# MCU.net
KiCad netlist of a schematic drawn in Altium Designer
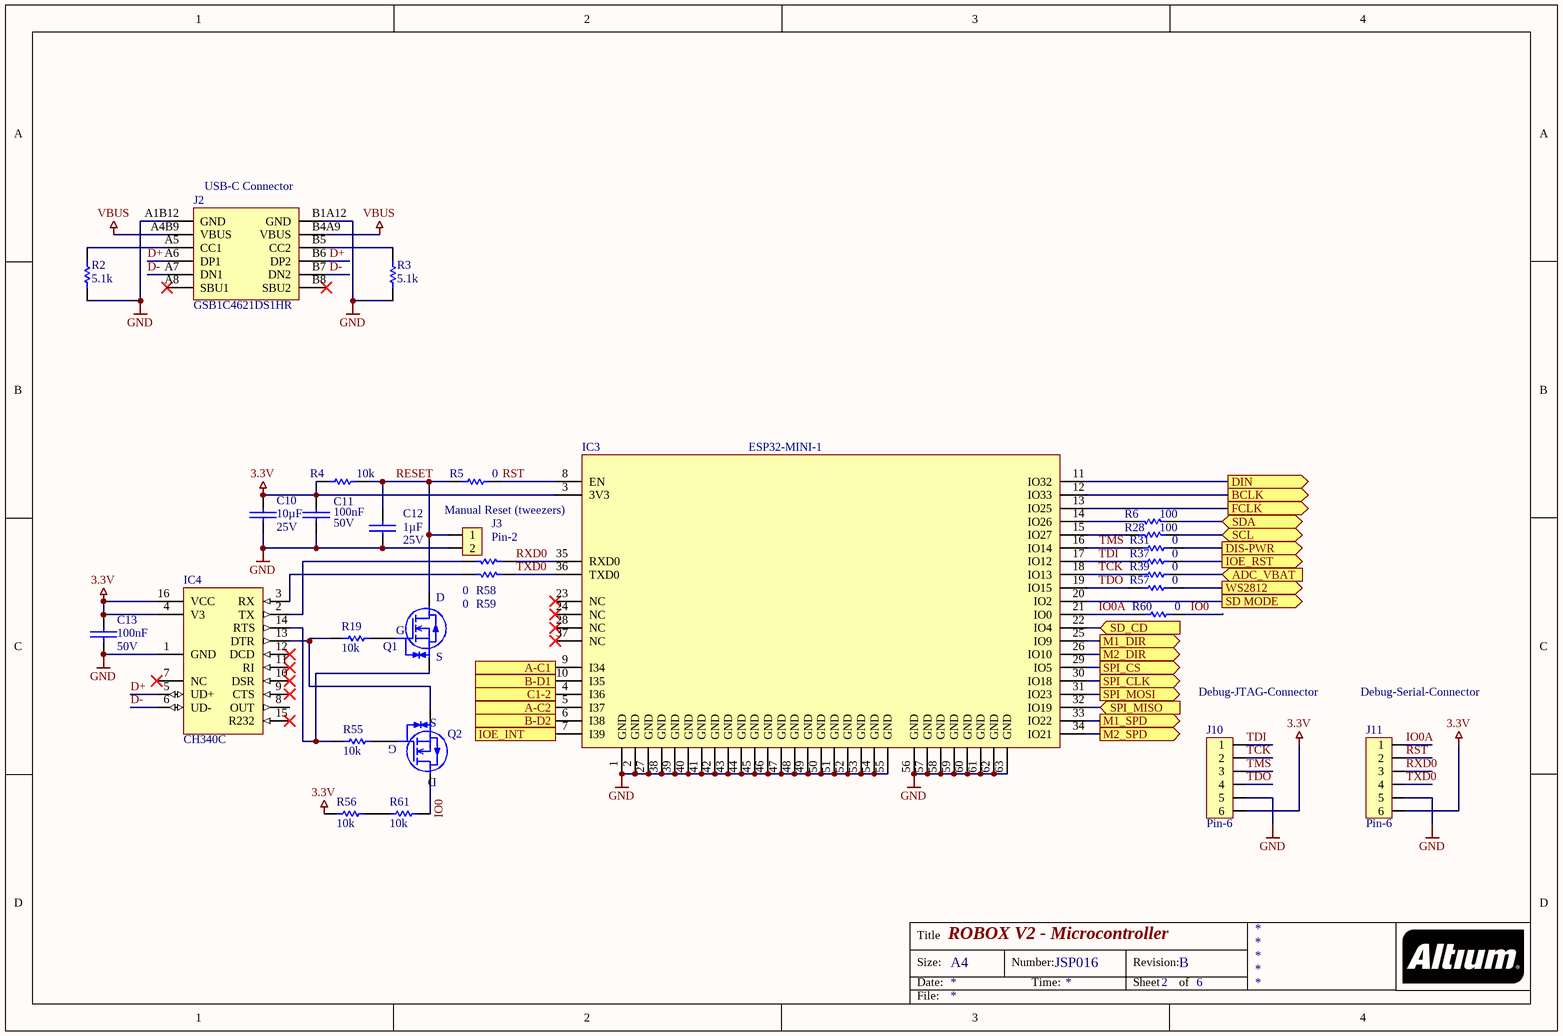
[diagram p0: MCU.SchDoc]

(export (version "E")
  (design (tool "Eeschema 10.0.6"))
  (components
    (comp (ref "C10")
      (value "10µF")
      (footprint "C0603")
      (description "CAP CER 10UF 25V X5R 10% SMD")
      (fields
        (field (name "MANUFACTURER") "Murata Electronics")
        (field (name "TOLERANCE") "10%")
        (field (name "VOLTAGE") "25V")
      )
      (libsource (lib "bond-altium-excell") (part "cap_non_pol"))
    )
    (comp (ref "C11")
      (value "100nF")
      (footprint "C0402")
      (description "CAP CER 0.1UF 50V X5R 0402")
      (fields
        (field (name "MANUFACTURER") "Murata Electronics")
        (field (name "TOLERANCE") "5%")
        (field (name "VOLTAGE") "50V")
      )
      (libsource (lib "bond-altium-excell") (part "cap_non_pol"))
    )
    (comp (ref "C12")
      (value "1µF")
      (footprint "C0603")
      (description "CAP CER 1UF 25V X5R 0603")
      (fields
        (field (name "MANUFACTURER") "YAGEO")
        (field (name "TOLERANCE") "10%")
        (field (name "VOLTAGE") "25V")
      )
      (libsource (lib "bond-altium-excell") (part "cap_non_pol"))
    )
    (comp (ref "C13")
      (value "100nF")
      (footprint "TH5.08")
      (description "CAP CER TH 100nF X7R 50V")
      (fields
        (field (name "MANUFACTURER") "FH")
        (field (name "TOLERANCE") "10%")
        (field (name "VOLTAGE") "50V")
      )
      (libsource (lib "bond-altium-excell") (part "cap_non_pol"))
    )
    (comp (ref "IC3")
      (value "ESP32-MINI-1")
      (footprint "ESP32-MINI-1")
      (description "RF TXRX MOD BT TRACE ANT CHAS MT")
      (fields (field (name "MANUFACTURER") "Espressif Systems"))
      (libsource (lib "bond-altium-excell") (part "ESP32-MINI-1"))
    )
    (comp (ref "IC4")
      (value "CH340C")
      (footprint "SOP-16")
      (description "2Mbps Transceiver USB 2.0 SOP-16 USB ICs ROHS")
      (fields (field (name "MANUFACTURER") "WCH(Jiangsu Qin Heng)"))
      (libsource (lib "bond-altium-excell") (part "CH340C"))
    )
    (comp (ref "J2")
      (value "GSB1C4621DS1HR")
      (footprint "GSB1C4621DS1HR")
      (description "USB2.0, TYPE C, MID MOUNT, CENTE")
      (fields (field (name "MANUFACTURER") "Amphenol ICC (Commercial Products)"))
      (libsource (lib "bond-altium-excell") (part "GSB1C4621DS1HR"))
    )
    (comp (ref "J3")
      (value "Pin-2")
      (footprint "2-PIN-EMPTY")
      (description "CONN TH solder pad")
      (libsource (lib "bond-altium-excell") (part "Pin-2"))
    )
    (comp (ref "J10")
      (value "Pin-6")
      (footprint "6-PIN-EMPTY")
      (description "CONN TH solder pad")
      (libsource (lib "bond-altium-excell") (part "Pin-6"))
    )
    (comp (ref "J11")
      (value "Pin-6")
      (footprint "6-PIN-EMPTY")
      (description "CONN TH solder pad")
      (libsource (lib "bond-altium-excell") (part "Pin-6"))
    )
    (comp (ref "Q1")
      (value "N_CH_MOSFET")
      (footprint "SOT-23(-3)")
      (description "MOSFET N-CH 100V 170MA SOT23-3")
      (fields (field (name "MANUFACTURER") "Diodes Incorporated"))
      (libsource (lib "bond-altium-excell") (part "N_CH_MOSFET"))
    )
    (comp (ref "Q2")
      (value "N_CH_MOSFET")
      (footprint "SOT-23(-3)")
      (description "MOSFET N-CH 100V 170MA SOT23-3")
      (fields (field (name "MANUFACTURER") "Diodes Incorporated"))
      (libsource (lib "bond-altium-excell") (part "N_CH_MOSFET"))
    )
    (comp (ref "R2")
      (value "5.1k")
      (footprint "R0402")
      (description "RES 5.1K OHM 1% 1/16W 0402")
      (fields (field (name "MANUFACTURER") "Stackpole Electronics Inc") (field (name "TOLERANCE") "1%"))
      (libsource (lib "bond-altium-excell") (part "resistor"))
    )
    (comp (ref "R3")
      (value "5.1k")
      (footprint "R0402")
      (description "RES 5.1K OHM 1% 1/16W 0402")
      (fields (field (name "MANUFACTURER") "Stackpole Electronics Inc") (field (name "TOLERANCE") "1%"))
      (libsource (lib "bond-altium-excell") (part "resistor"))
    )
    (comp (ref "R4")
      (value "10k")
      (footprint "R0402")
      (description "RES SMD 10K OHM 1% 1/10W 0402")
      (fields (field (name "MANUFACTURER") "Panasonic Electronic Components") (field (name "TOLERANCE") "1%"))
      (libsource (lib "bond-altium-excell") (part "resistor"))
    )
    (comp (ref "R5")
      (value "0")
      (footprint "R0402")
      (description "RES SMD 0 OHM JUMPER 1/10W 0402")
      (fields (field (name "MANUFACTURER") "Panasonic Electronic Components") (field (name "TOLERANCE") "1%"))
      (libsource (lib "bond-altium-excell") (part "resistor"))
    )
    (comp (ref "R6")
      (value "100")
      (footprint "R0402")
      (description "RES SMD 100 OHM 1% 1/5W 0402")
      (fields (field (name "MANUFACTURER") "Vishay Dale") (field (name "TOLERANCE") "1%"))
      (libsource (lib "bond-altium-excell") (part "resistor"))
    )
    (comp (ref "R19")
      (value "10k")
      (footprint "R0402")
      (description "RES SMD 10K OHM 1% 1/10W 0402")
      (fields (field (name "MANUFACTURER") "Panasonic Electronic Components") (field (name "TOLERANCE") "1%"))
      (libsource (lib "bond-altium-excell") (part "resistor"))
    )
    (comp (ref "R28")
      (value "100")
      (footprint "R0402")
      (description "RES SMD 100 OHM 1% 1/5W 0402")
      (fields (field (name "MANUFACTURER") "Vishay Dale") (field (name "TOLERANCE") "1%"))
      (libsource (lib "bond-altium-excell") (part "resistor"))
    )
    (comp (ref "R31")
      (value "0")
      (footprint "R0402")
      (description "RES SMD 0 OHM JUMPER 1/10W 0402")
      (fields (field (name "MANUFACTURER") "Panasonic Electronic Components") (field (name "TOLERANCE") "1%"))
      (libsource (lib "bond-altium-excell") (part "resistor"))
    )
    (comp (ref "R37")
      (value "0")
      (footprint "R0402")
      (description "RES SMD 0 OHM JUMPER 1/10W 0402")
      (fields (field (name "MANUFACTURER") "Panasonic Electronic Components") (field (name "TOLERANCE") "1%"))
      (libsource (lib "bond-altium-excell") (part "resistor"))
    )
    (comp (ref "R39")
      (value "0")
      (footprint "R0402")
      (description "RES SMD 0 OHM JUMPER 1/10W 0402")
      (fields (field (name "MANUFACTURER") "Panasonic Electronic Components") (field (name "TOLERANCE") "1%"))
      (libsource (lib "bond-altium-excell") (part "resistor"))
    )
    (comp (ref "R55")
      (value "10k")
      (footprint "R0402")
      (description "RES SMD 10K OHM 1% 1/10W 0402")
      (fields (field (name "MANUFACTURER") "Panasonic Electronic Components") (field (name "TOLERANCE") "1%"))
      (libsource (lib "bond-altium-excell") (part "resistor"))
    )
    (comp (ref "R56")
      (value "10k")
      (footprint "R0402")
      (description "RES SMD 10K OHM 1% 1/10W 0402")
      (fields (field (name "MANUFACTURER") "Panasonic Electronic Components") (field (name "TOLERANCE") "1%"))
      (libsource (lib "bond-altium-excell") (part "resistor"))
    )
    (comp (ref "R57")
      (value "0")
      (footprint "R0402")
      (description "RES SMD 0 OHM JUMPER 1/10W 0402")
      (fields (field (name "MANUFACTURER") "Panasonic Electronic Components") (field (name "TOLERANCE") "1%"))
      (libsource (lib "bond-altium-excell") (part "resistor"))
    )
    (comp (ref "R58")
      (value "0")
      (footprint "R0402")
      (description "RES SMD 0 OHM JUMPER 1/10W 0402")
      (fields (field (name "MANUFACTURER") "Panasonic Electronic Components") (field (name "TOLERANCE") "1%"))
      (libsource (lib "bond-altium-excell") (part "resistor"))
    )
    (comp (ref "R59")
      (value "0")
      (footprint "R0402")
      (description "RES SMD 0 OHM JUMPER 1/10W 0402")
      (fields (field (name "MANUFACTURER") "Panasonic Electronic Components") (field (name "TOLERANCE") "1%"))
      (libsource (lib "bond-altium-excell") (part "resistor"))
    )
    (comp (ref "R60")
      (value "0")
      (footprint "R0402")
      (description "RES SMD 0 OHM JUMPER 1/10W 0402")
      (fields (field (name "MANUFACTURER") "Panasonic Electronic Components") (field (name "TOLERANCE") "1%"))
      (libsource (lib "bond-altium-excell") (part "resistor"))
    )
    (comp (ref "R61")
      (value "10k")
      (footprint "R0402")
      (description "RES SMD 10K OHM 1% 1/10W 0402")
      (fields (field (name "MANUFACTURER") "Panasonic Electronic Components") (field (name "TOLERANCE") "1%"))
      (libsource (lib "bond-altium-excell") (part "resistor"))
    )
  )
  (nets
    (net (code "1") (name "/A-C1") (class "Default")
      (node (ref "IC3") (pin "9") (pinfunction "I34_9") (pintype "passive"))
    )
    (net (code "2") (name "/A-C2") (class "Default")
      (node (ref "IC3") (pin "5") (pinfunction "I37_5") (pintype "passive"))
    )
    (net (code "3") (name "/ADC_VBAT") (class "Default")
      (node (ref "R39") (pin "1") (pinfunction "1_1") (pintype "passive"))
    )
    (net (code "4") (name "/B-D1") (class "Default")
      (node (ref "IC3") (pin "10") (pinfunction "I35_10") (pintype "passive"))
    )
    (net (code "5") (name "/B-D2") (class "Default")
      (node (ref "IC3") (pin "6") (pinfunction "I38_6") (pintype "passive"))
    )
    (net (code "6") (name "/BCLK") (class "Default")
      (node (ref "IC3") (pin "12") (pinfunction "IO33_12") (pintype "passive"))
    )
    (net (code "7") (name "/C1-2") (class "Default")
      (node (ref "IC3") (pin "4") (pinfunction "I36_4") (pintype "passive"))
    )
    (net (code "8") (name "/D+") (class "Default")
      (node (ref "IC4") (pin "5") (pinfunction "UD+_5") (pintype "bidirectional"))
      (node (ref "J2") (pin "A6") (pinfunction "DP1_A6") (pintype "passive"))
      (node (ref "J2") (pin "B6") (pinfunction "DP2_B6") (pintype "passive"))
    )
    (net (code "9") (name "/D-") (class "Default")
      (node (ref "IC4") (pin "6") (pinfunction "UD-_6") (pintype "bidirectional"))
      (node (ref "J2") (pin "A7") (pinfunction "DN1_A7") (pintype "passive"))
      (node (ref "J2") (pin "B7") (pinfunction "DN2_B7") (pintype "passive"))
    )
    (net (code "10") (name "/DIN") (class "Default")
      (node (ref "IC3") (pin "11") (pinfunction "IO32_11") (pintype "passive"))
    )
    (net (code "11") (name "/DIS-PWR") (class "Default")
      (node (ref "R31") (pin "1") (pinfunction "1_1") (pintype "passive"))
    )
    (net (code "12") (name "/FCLK") (class "Default")
      (node (ref "IC3") (pin "13") (pinfunction "IO25_13") (pintype "passive"))
    )
    (net (code "13") (name "/IO0") (class "Default")
      (node (ref "Q2") (pin "3") (pinfunction "D_3") (pintype "passive"))
      (node (ref "R60") (pin "1") (pinfunction "1_1") (pintype "passive"))
      (node (ref "R61") (pin "2") (pinfunction "2_2") (pintype "passive"))
    )
    (net (code "14") (name "/IO0A") (class "Default")
      (node (ref "IC3") (pin "21") (pinfunction "IO0_21") (pintype "passive"))
      (node (ref "J11") (pin "1") (pinfunction "1_1") (pintype "passive"))
      (node (ref "R60") (pin "2") (pinfunction "2_2") (pintype "passive"))
    )
    (net (code "15") (name "/IOE_INT") (class "Default")
      (node (ref "IC3") (pin "7") (pinfunction "I39_7") (pintype "passive"))
    )
    (net (code "16") (name "/IOE_RST") (class "Default")
      (node (ref "R37") (pin "1") (pinfunction "1_1") (pintype "passive"))
    )
    (net (code "17") (name "/M1_DIR") (class "Default")
      (node (ref "IC3") (pin "25") (pinfunction "IO9_25") (pintype "passive"))
    )
    (net (code "18") (name "/M1_SPD") (class "Default")
      (node (ref "IC3") (pin "33") (pinfunction "IO22_33") (pintype "passive"))
    )
    (net (code "19") (name "/M2_DIR") (class "Default")
      (node (ref "IC3") (pin "26") (pinfunction "IO10_26") (pintype "passive"))
    )
    (net (code "20") (name "/M2_SPD") (class "Default")
      (node (ref "IC3") (pin "34") (pinfunction "IO21_34") (pintype "passive"))
    )
    (net (code "21") (name "/RESET") (class "Default")
      (node (ref "C12") (pin "1") (pinfunction "1_1") (pintype "passive"))
      (node (ref "J3") (pin "1") (pinfunction "1_1") (pintype "passive"))
      (node (ref "Q1") (pin "3") (pinfunction "D_3") (pintype "passive"))
      (node (ref "R4") (pin "1") (pinfunction "1_1") (pintype "passive"))
      (node (ref "R5") (pin "2") (pinfunction "2_2") (pintype "passive"))
    )
    (net (code "22") (name "/RST") (class "Default")
      (node (ref "IC3") (pin "8") (pinfunction "EN_8") (pintype "passive"))
      (node (ref "J11") (pin "2") (pinfunction "2_2") (pintype "passive"))
      (node (ref "R5") (pin "1") (pinfunction "1_1") (pintype "passive"))
    )
    (net (code "23") (name "/RXD0") (class "Default")
      (node (ref "IC3") (pin "35") (pinfunction "RXD0_35") (pintype "passive"))
      (node (ref "J11") (pin "3") (pinfunction "3_3") (pintype "passive"))
      (node (ref "R58") (pin "1") (pinfunction "1_1") (pintype "passive"))
    )
    (net (code "24") (name "/SCL") (class "Default")
      (node (ref "R28") (pin "2") (pinfunction "2_2") (pintype "passive"))
    )
    (net (code "25") (name "/SD MODE") (class "Default")
      (node (ref "IC3") (pin "20") (pinfunction "IO2_20") (pintype "passive"))
    )
    (net (code "26") (name "/SDA") (class "Default")
      (node (ref "R6") (pin "2") (pinfunction "2_2") (pintype "passive"))
    )
    (net (code "27") (name "/SD_CD") (class "Default")
      (node (ref "IC3") (pin "22") (pinfunction "IO4_22") (pintype "passive"))
    )
    (net (code "28") (name "/SPI_CLK") (class "Default")
      (node (ref "IC3") (pin "30") (pinfunction "IO18_30") (pintype "passive"))
    )
    (net (code "29") (name "/SPI_CS") (class "Default")
      (node (ref "IC3") (pin "29") (pinfunction "IO5_29") (pintype "passive"))
    )
    (net (code "30") (name "/SPI_MISO") (class "Default")
      (node (ref "IC3") (pin "32") (pinfunction "IO19_32") (pintype "passive"))
    )
    (net (code "31") (name "/SPI_MOSI") (class "Default")
      (node (ref "IC3") (pin "31") (pinfunction "IO23_31") (pintype "passive"))
    )
    (net (code "32") (name "/TCK") (class "Default")
      (node (ref "IC3") (pin "18") (pinfunction "IO13_18") (pintype "passive"))
      (node (ref "J10") (pin "2") (pinfunction "2_2") (pintype "passive"))
      (node (ref "R39") (pin "2") (pinfunction "2_2") (pintype "passive"))
    )
    (net (code "33") (name "/TDI") (class "Default")
      (node (ref "IC3") (pin "17") (pinfunction "IO12_17") (pintype "passive"))
      (node (ref "J10") (pin "1") (pinfunction "1_1") (pintype "passive"))
      (node (ref "R37") (pin "2") (pinfunction "2_2") (pintype "passive"))
    )
    (net (code "34") (name "/TDO") (class "Default")
      (node (ref "IC3") (pin "19") (pinfunction "IO15_19") (pintype "passive"))
      (node (ref "J10") (pin "4") (pinfunction "4_4") (pintype "passive"))
      (node (ref "R57") (pin "2") (pinfunction "2_2") (pintype "passive"))
    )
    (net (code "35") (name "/TMS") (class "Default")
      (node (ref "IC3") (pin "16") (pinfunction "IO14_16") (pintype "passive"))
      (node (ref "J10") (pin "3") (pinfunction "3_3") (pintype "passive"))
      (node (ref "R31") (pin "2") (pinfunction "2_2") (pintype "passive"))
    )
    (net (code "36") (name "/TXD0") (class "Default")
      (node (ref "IC3") (pin "36") (pinfunction "TXD0_36") (pintype "passive"))
      (node (ref "J11") (pin "4") (pinfunction "4_4") (pintype "passive"))
      (node (ref "R59") (pin "1") (pinfunction "1_1") (pintype "passive"))
    )
    (net (code "37") (name "/WS2812") (class "Default")
      (node (ref "R57") (pin "1") (pinfunction "1_1") (pintype "passive"))
    )
    (net (code "38") (name "3.3V") (class "Default")
      (node (ref "C10") (pin "1") (pinfunction "1_1") (pintype "passive"))
      (node (ref "C11") (pin "2") (pinfunction "2_2") (pintype "passive"))
      (node (ref "C13") (pin "1") (pinfunction "1_1") (pintype "passive"))
      (node (ref "IC3") (pin "3") (pinfunction "3V3_3") (pintype "passive"))
      (node (ref "IC4") (pin "16") (pinfunction "VCC_16") (pintype "power_in"))
      (node (ref "IC4") (pin "4") (pinfunction "V3_4") (pintype "power_in"))
      (node (ref "J10") (pin "6") (pinfunction "6_6") (pintype "passive"))
      (node (ref "J11") (pin "6") (pinfunction "6_6") (pintype "passive"))
      (node (ref "R4") (pin "2") (pinfunction "2_2") (pintype "passive"))
      (node (ref "R56") (pin "1") (pinfunction "1_1") (pintype "passive"))
    )
    (net (code "39") (name "GND") (class "Default")
      (node (ref "C10") (pin "2") (pinfunction "2_2") (pintype "passive"))
      (node (ref "C11") (pin "1") (pinfunction "1_1") (pintype "passive"))
      (node (ref "C12") (pin "2") (pinfunction "2_2") (pintype "passive"))
      (node (ref "C13") (pin "2") (pinfunction "2_2") (pintype "passive"))
      (node (ref "IC3") (pin "1") (pinfunction "GND_1") (pintype "passive"))
      (node (ref "IC3") (pin "2") (pinfunction "GND_2") (pintype "passive"))
      (node (ref "IC3") (pin "27") (pinfunction "GND_27") (pintype "passive"))
      (node (ref "IC3") (pin "38") (pinfunction "GND_38") (pintype "passive"))
      (node (ref "IC3") (pin "39") (pinfunction "GND_39") (pintype "passive"))
      (node (ref "IC3") (pin "40") (pinfunction "GND_40") (pintype "passive"))
      (node (ref "IC3") (pin "41") (pinfunction "GND_41") (pintype "passive"))
      (node (ref "IC3") (pin "42") (pinfunction "GND_42") (pintype "passive"))
      (node (ref "IC3") (pin "43") (pinfunction "GND_43") (pintype "passive"))
      (node (ref "IC3") (pin "44") (pinfunction "GND_44") (pintype "passive"))
      (node (ref "IC3") (pin "45") (pinfunction "GND_45") (pintype "passive"))
      (node (ref "IC3") (pin "46") (pinfunction "GND_46") (pintype "passive"))
      (node (ref "IC3") (pin "47") (pinfunction "GND_47") (pintype "passive"))
      (node (ref "IC3") (pin "48") (pinfunction "GND_48") (pintype "passive"))
      (node (ref "IC3") (pin "49") (pinfunction "GND_49") (pintype "passive"))
      (node (ref "IC3") (pin "50") (pinfunction "GND_50") (pintype "passive"))
      (node (ref "IC3") (pin "51") (pinfunction "GND_51") (pintype "passive"))
      (node (ref "IC3") (pin "52") (pinfunction "GND_52") (pintype "passive"))
      (node (ref "IC3") (pin "53") (pinfunction "GND_53") (pintype "passive"))
      (node (ref "IC3") (pin "54") (pinfunction "GND_54") (pintype "passive"))
      (node (ref "IC3") (pin "55") (pinfunction "GND_55") (pintype "passive"))
      (node (ref "IC3") (pin "56") (pinfunction "GND_56") (pintype "passive"))
      (node (ref "IC3") (pin "57") (pinfunction "GND_57") (pintype "passive"))
      (node (ref "IC3") (pin "58") (pinfunction "GND_58") (pintype "passive"))
      (node (ref "IC3") (pin "59") (pinfunction "GND_59") (pintype "passive"))
      (node (ref "IC3") (pin "60") (pinfunction "GND_60") (pintype "passive"))
      (node (ref "IC3") (pin "61") (pinfunction "GND_61") (pintype "passive"))
      (node (ref "IC3") (pin "62") (pinfunction "GND_62") (pintype "passive"))
      (node (ref "IC3") (pin "63") (pinfunction "GND_63") (pintype "passive"))
      (node (ref "IC4") (pin "1") (pinfunction "GND_1") (pintype "power_in"))
      (node (ref "J10") (pin "5") (pinfunction "5_5") (pintype "passive"))
      (node (ref "J11") (pin "5") (pinfunction "5_5") (pintype "passive"))
      (node (ref "J2") (pin "A1B12") (pinfunction "GND_A1B12") (pintype "passive"))
      (node (ref "J2") (pin "B1A12") (pinfunction "GND_B1A12") (pintype "passive"))
      (node (ref "J3") (pin "2") (pinfunction "2_2") (pintype "passive"))
      (node (ref "R2") (pin "2") (pinfunction "2_2") (pintype "passive"))
      (node (ref "R3") (pin "2") (pinfunction "2_2") (pintype "passive"))
    )
    (net (code "40") (name "Net-(IC3-IO26)") (class "Default")
      (node (ref "IC3") (pin "14") (pinfunction "IO26_14") (pintype "passive"))
      (node (ref "R6") (pin "1") (pinfunction "1_1") (pintype "passive"))
    )
    (net (code "41") (name "Net-(IC3-IO27)") (class "Default")
      (node (ref "IC3") (pin "15") (pinfunction "IO27_15") (pintype "passive"))
      (node (ref "R28") (pin "1") (pinfunction "1_1") (pintype "passive"))
    )
    (net (code "42") (name "Net-(IC4-DTR)") (class "Default")
      (node (ref "IC4") (pin "13") (pinfunction "DTR_13") (pintype "output"))
      (node (ref "Q2") (pin "2") (pinfunction "S_2") (pintype "passive"))
      (node (ref "R19") (pin "1") (pinfunction "1_1") (pintype "passive"))
    )
    (net (code "43") (name "Net-(IC4-RTS)") (class "Default")
      (node (ref "IC4") (pin "14") (pinfunction "RTS_14") (pintype "output"))
      (node (ref "Q1") (pin "2") (pinfunction "S_2") (pintype "passive"))
      (node (ref "R55") (pin "1") (pinfunction "1_1") (pintype "passive"))
    )
    (net (code "44") (name "Net-(IC4-RX)") (class "Default")
      (node (ref "IC4") (pin "3") (pinfunction "RX_3") (pintype "input"))
      (node (ref "R59") (pin "2") (pinfunction "2_2") (pintype "passive"))
    )
    (net (code "45") (name "Net-(IC4-TX)") (class "Default")
      (node (ref "IC4") (pin "2") (pinfunction "TX_2") (pintype "output"))
      (node (ref "R58") (pin "2") (pinfunction "2_2") (pintype "passive"))
    )
    (net (code "46") (name "Net-(J2-CC1)") (class "Default")
      (node (ref "J2") (pin "A5") (pinfunction "CC1_A5") (pintype "passive"))
      (node (ref "R2") (pin "1") (pinfunction "1_1") (pintype "passive"))
    )
    (net (code "47") (name "Net-(J2-CC2)") (class "Default")
      (node (ref "J2") (pin "B5") (pinfunction "CC2_B5") (pintype "passive"))
      (node (ref "R3") (pin "1") (pinfunction "1_1") (pintype "passive"))
    )
    (net (code "48") (name "Net-(Q1-G)") (class "Default")
      (node (ref "Q1") (pin "1") (pinfunction "G_1") (pintype "passive"))
      (node (ref "R19") (pin "2") (pinfunction "2_2") (pintype "passive"))
    )
    (net (code "49") (name "Net-(Q2-G)") (class "Default")
      (node (ref "Q2") (pin "1") (pinfunction "G_1") (pintype "passive"))
      (node (ref "R55") (pin "2") (pinfunction "2_2") (pintype "passive"))
    )
    (net (code "50") (name "Net-(R56-Pad2)") (class "Default")
      (node (ref "R56") (pin "2") (pinfunction "2_2") (pintype "passive"))
      (node (ref "R61") (pin "1") (pinfunction "1_1") (pintype "passive"))
    )
    (net (code "51") (name "VBUS") (class "Default")
      (node (ref "J2") (pin "A4B9") (pinfunction "VBUS_A4B9") (pintype "passive"))
      (node (ref "J2") (pin "B4A9") (pinfunction "VBUS_B4A9") (pintype "passive"))
    )
    (net (code "52") (name "unconnected-(IC3-NC-Pad23)") (class "Default")
      (node (ref "IC3") (pin "23") (pinfunction "NC_23") (pintype "passive+no_connect"))
    )
    (net (code "53") (name "unconnected-(IC3-NC-Pad24)") (class "Default")
      (node (ref "IC3") (pin "24") (pinfunction "NC_24") (pintype "passive+no_connect"))
    )
    (net (code "54") (name "unconnected-(IC3-NC-Pad28)") (class "Default")
      (node (ref "IC3") (pin "28") (pinfunction "NC_28") (pintype "passive+no_connect"))
    )
    (net (code "55") (name "unconnected-(IC3-NC-Pad37)") (class "Default")
      (node (ref "IC3") (pin "37") (pinfunction "NC_37") (pintype "passive+no_connect"))
    )
    (net (code "56") (name "unconnected-(IC4-CTS-Pad9)") (class "Default")
      (node (ref "IC4") (pin "9") (pinfunction "CTS_9") (pintype "input+no_connect"))
    )
    (net (code "57") (name "unconnected-(IC4-DCD-Pad12)") (class "Default")
      (node (ref "IC4") (pin "12") (pinfunction "DCD_12") (pintype "input+no_connect"))
    )
    (net (code "58") (name "unconnected-(IC4-DSR-Pad10)") (class "Default")
      (node (ref "IC4") (pin "10") (pinfunction "DSR_10") (pintype "input+no_connect"))
    )
    (net (code "59") (name "unconnected-(IC4-NC-Pad7)") (class "Default")
      (node (ref "IC4") (pin "7") (pinfunction "NC_7") (pintype "passive+no_connect"))
    )
    (net (code "60") (name "unconnected-(IC4-OUT-Pad8)") (class "Default")
      (node (ref "IC4") (pin "8") (pinfunction "OUT_8") (pintype "output"))
    )
    (net (code "61") (name "unconnected-(IC4-R232-Pad15)") (class "Default")
      (node (ref "IC4") (pin "15") (pinfunction "R232_15") (pintype "input+no_connect"))
    )
    (net (code "62") (name "unconnected-(IC4-RI-Pad11)") (class "Default")
      (node (ref "IC4") (pin "11") (pinfunction "RI_11") (pintype "input+no_connect"))
    )
    (net (code "63") (name "unconnected-(J2-SBU1-PadA8)") (class "Default")
      (node (ref "J2") (pin "A8") (pinfunction "SBU1_A8") (pintype "passive"))
    )
    (net (code "64") (name "unconnected-(J2-SBU2-PadB8)") (class "Default")
      (node (ref "J2") (pin "B8") (pinfunction "SBU2_B8") (pintype "passive"))
    )
  )
)
